# pulseHPT.net
KiCad netlist of a schematic drawn in EAGLE
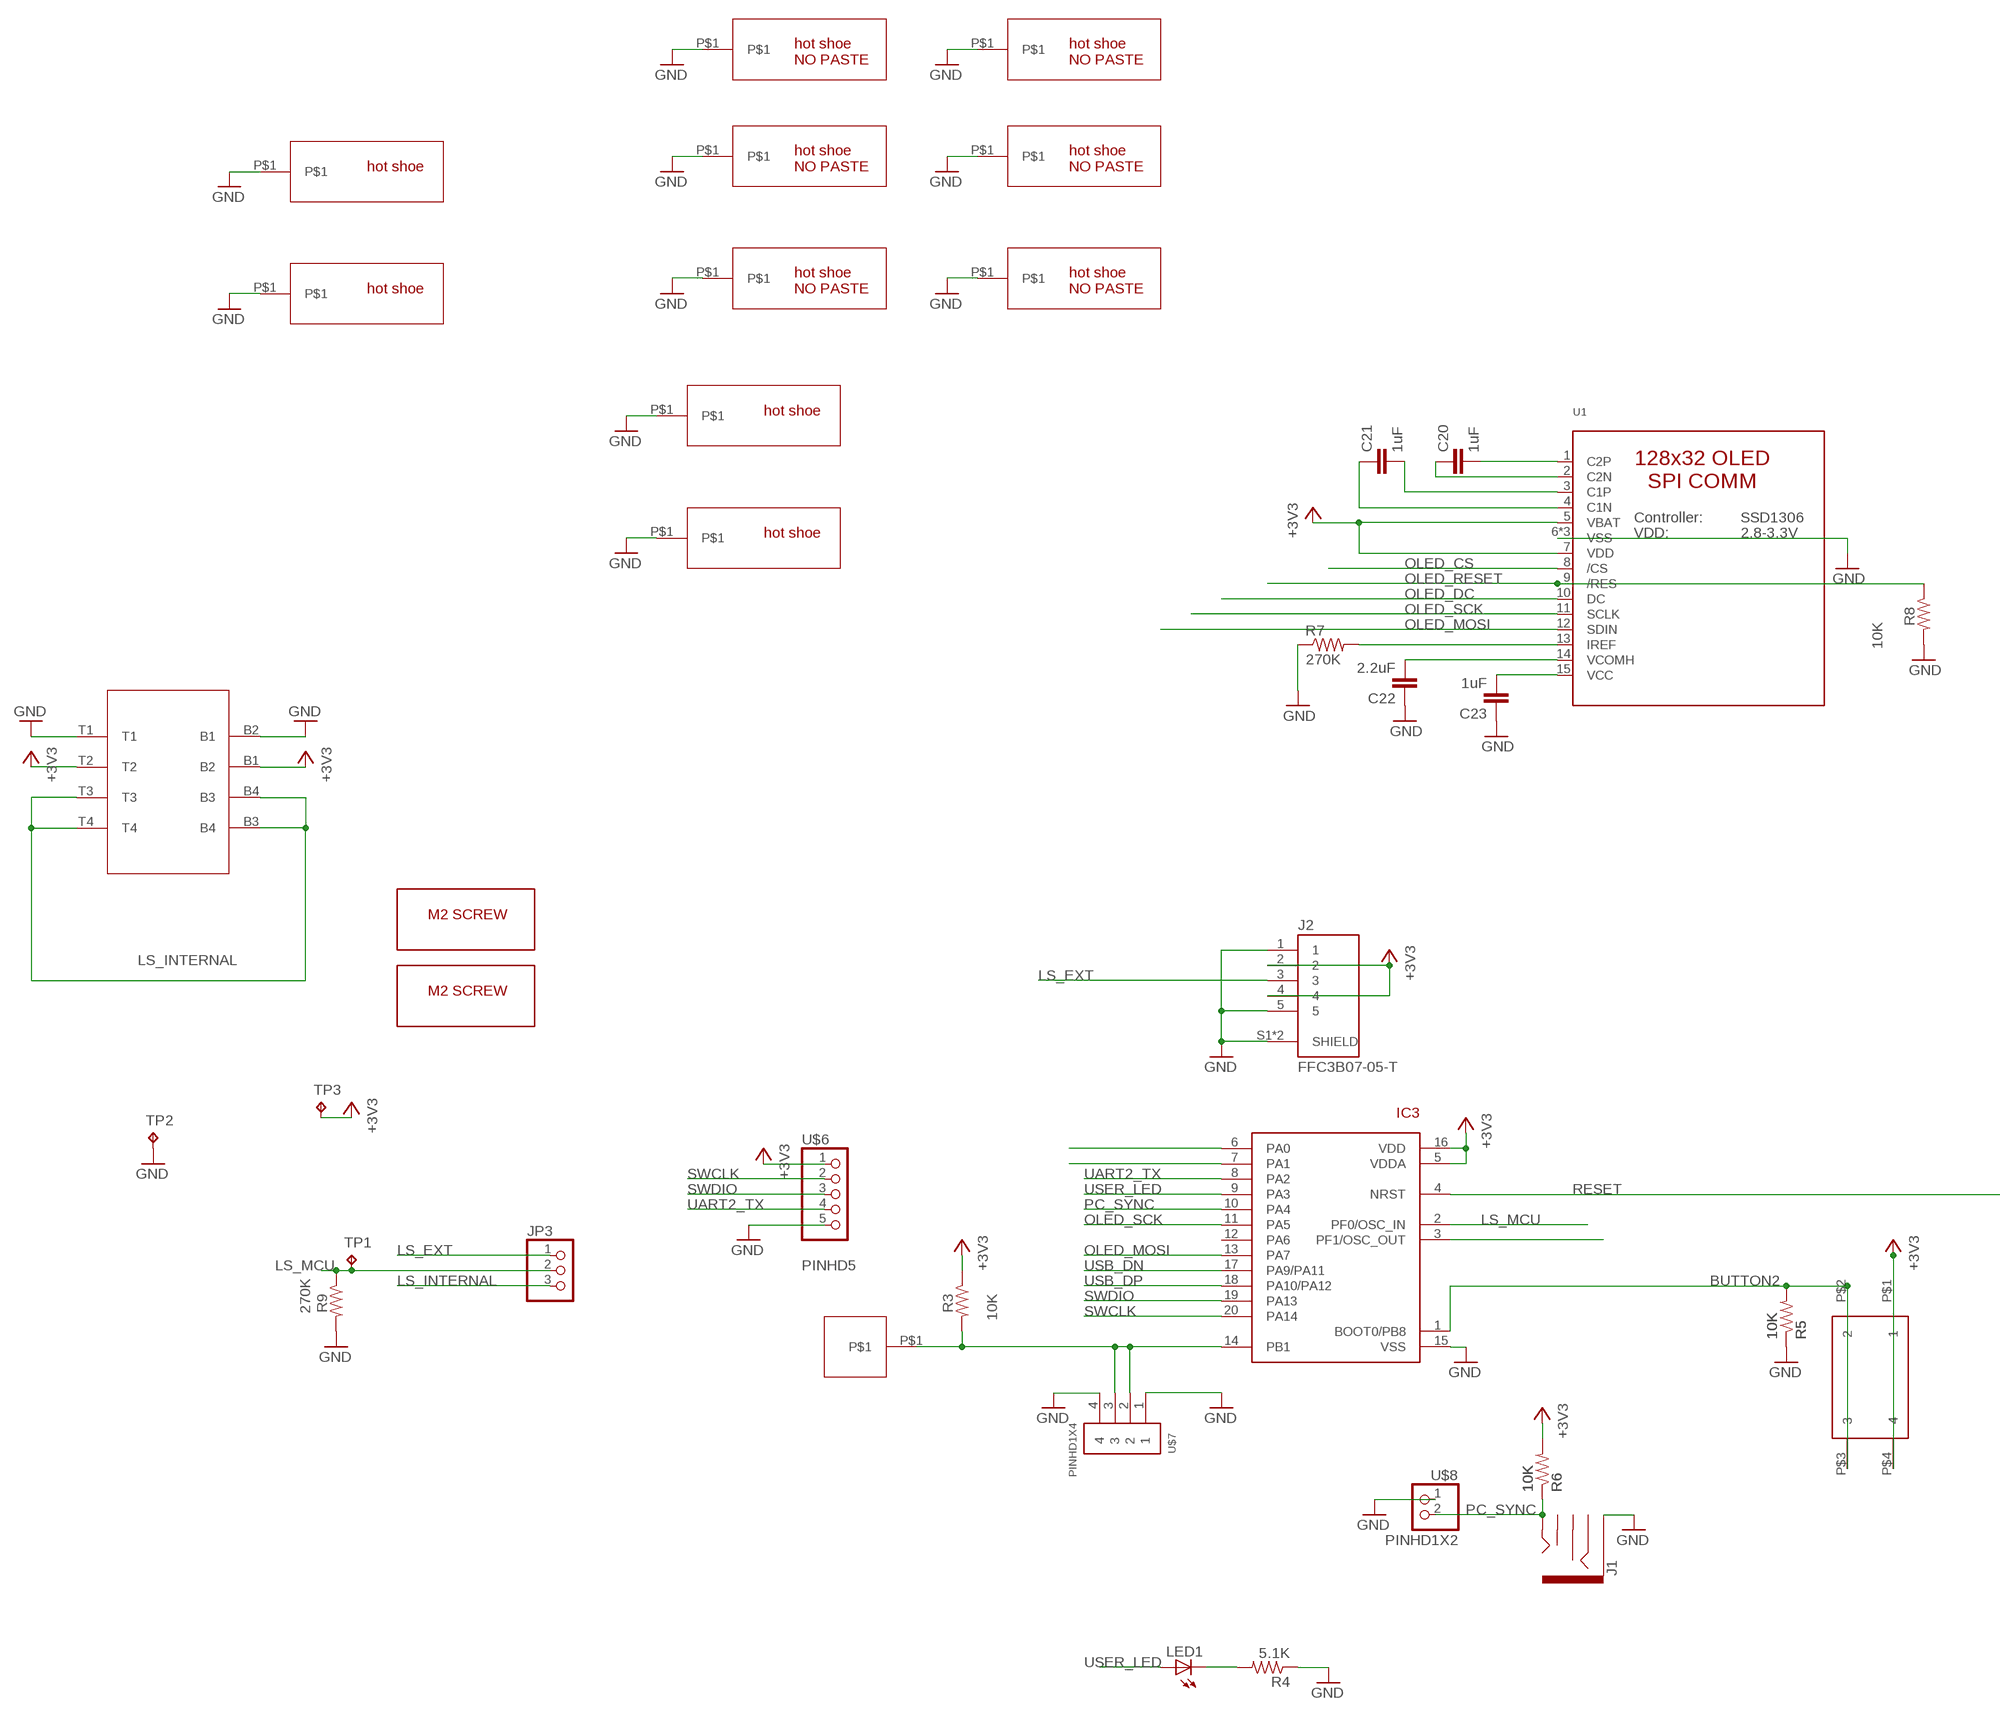
[diagram p0: schematic, sheet 1, part 1 of 2]
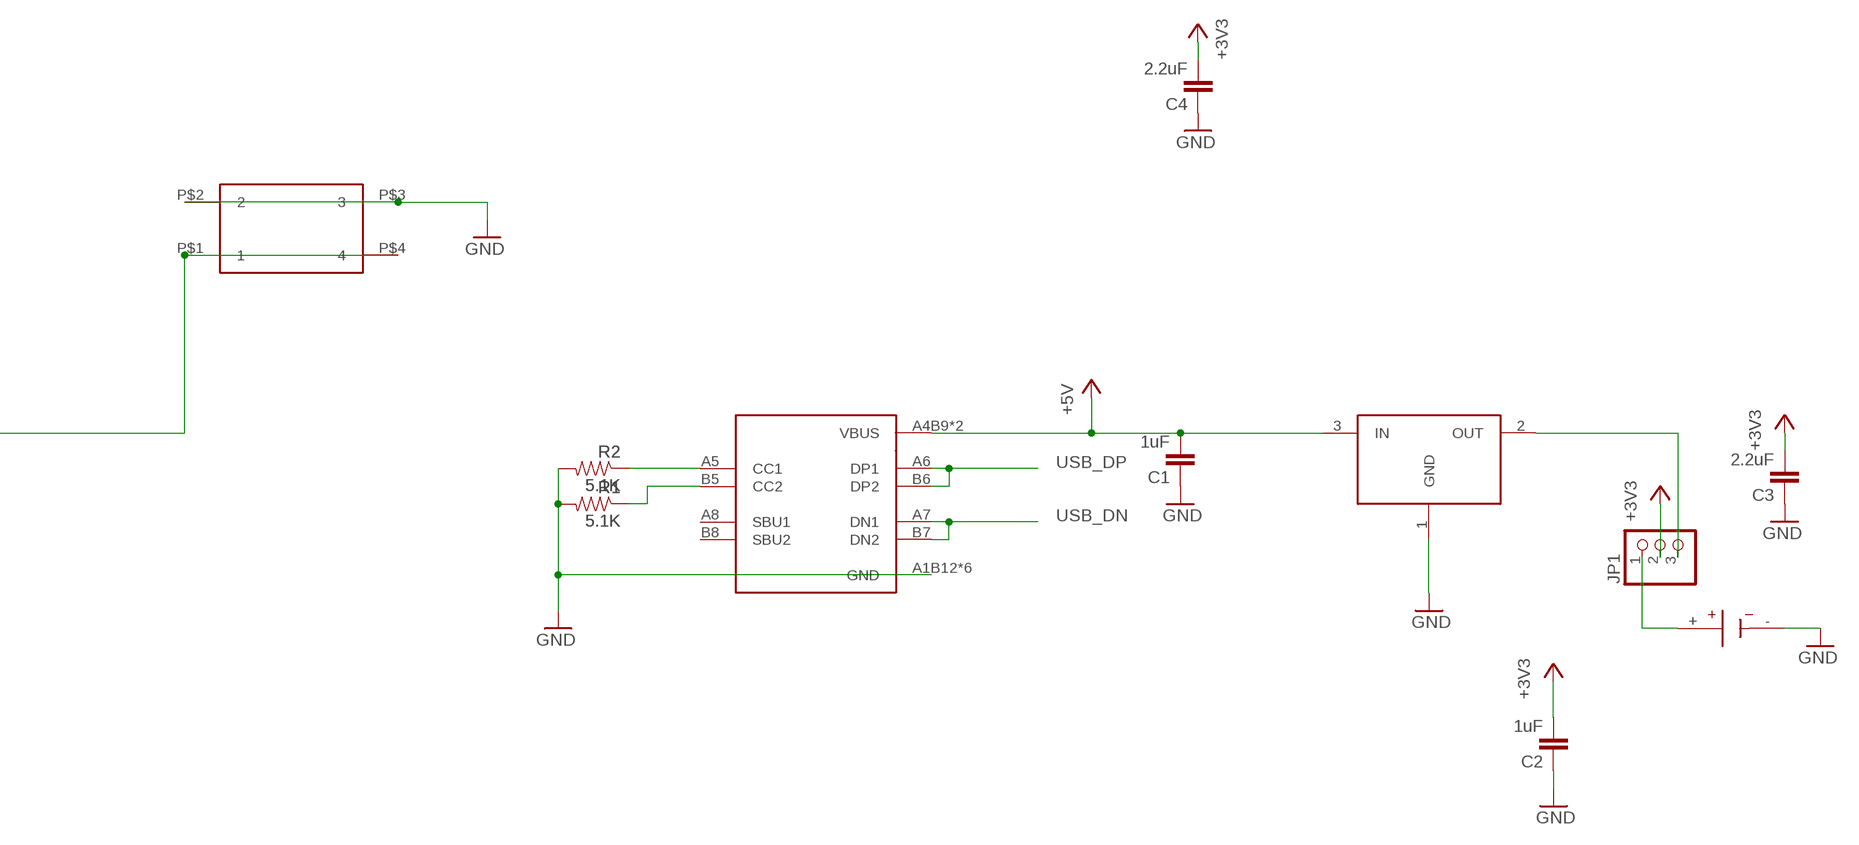
[diagram p1: schematic, sheet 1, part 2 of 2]

(export (version "E")
  (design (tool "Eeschema 10.0.6"))
  (components
    (comp (ref "BT1")
      (value "BU2032SM-G")
      (footprint "eagle-import:BAT_BU2032SM-G")
      (fields (field (name "MF") "MPD"))
      (libsource (lib "eagle-import") (part "BU2032SM-G"))
    )
    (comp (ref "C1")
      (value "1uF")
      (footprint "eagle-import:0805")
      (libsource (lib "eagle-import") (part "CAP0805"))
    )
    (comp (ref "C2")
      (value "1uF")
      (footprint "eagle-import:0805")
      (libsource (lib "eagle-import") (part "CAP0805"))
    )
    (comp (ref "C3")
      (value "2.2uF")
      (footprint "eagle-import:0805")
      (libsource (lib "eagle-import") (part "CAP0805"))
    )
    (comp (ref "C4")
      (value "2.2uF")
      (footprint "eagle-import:0805")
      (libsource (lib "eagle-import") (part "CAP0805"))
    )
    (comp (ref "C20")
      (value "1uF")
      (footprint "eagle-import:0805")
      (libsource (lib "eagle-import") (part "CAP0805"))
    )
    (comp (ref "C21")
      (value "1uF")
      (footprint "eagle-import:0805")
      (libsource (lib "eagle-import") (part "CAP0805"))
    )
    (comp (ref "C22")
      (value "2.2uF")
      (footprint "eagle-import:0805")
      (libsource (lib "eagle-import") (part "CAP0805"))
    )
    (comp (ref "C23")
      (value "1uF")
      (footprint "eagle-import:0805")
      (libsource (lib "eagle-import") (part "CAP0805"))
    )
    (comp (ref "IC3")
      (value "STM32F042F4")
      (footprint "eagle-import:TSSOP20")
      (libsource (lib "eagle-import") (part "STM32F042F4"))
    )
    (comp (ref "J1")
      (value "AUDIO_JACK_3.5MM_PTH")
      (footprint "eagle-import:AUDIO-JACK")
      (libsource (lib "eagle-import") (part "AUDIO_JACK_3.5MM_PTH"))
    )
    (comp (ref "J2")
      (value "FFC3B07-05-T")
      (footprint "eagle-import:GCT_FFC3B07-05-T")
      (fields (field (name "MF") "Global Connector Technology"))
      (libsource (lib "eagle-import") (part "FFC3B07-05-T"))
    )
    (comp (ref "JP1")
      (value "PINHD-1X3CB")
      (footprint "eagle-import:1X03-CLEANBIG")
      (libsource (lib "eagle-import") (part "PINHD-1X3CB"))
    )
    (comp (ref "JP3")
      (value "PINHD-1X3CB")
      (footprint "eagle-import:1X03-CLEANBIG")
      (libsource (lib "eagle-import") (part "PINHD-1X3CB"))
    )
    (comp (ref "LED1")
      (value "LEDCHIP-LED0805")
      (footprint "eagle-import:CHIP-LED0805")
      (libsource (lib "eagle-import") (part "LEDCHIP-LED0805"))
    )
    (comp (ref "R1")
      (value "5.1K")
      (footprint "eagle-import:0805")
      (libsource (lib "eagle-import") (part "joyAnalog_RESISTOR0805-RES"))
    )
    (comp (ref "R2")
      (value "5.1K")
      (footprint "eagle-import:0805")
      (libsource (lib "eagle-import") (part "joyAnalog_RESISTOR0805-RES"))
    )
    (comp (ref "R3")
      (value "10K")
      (footprint "eagle-import:0805")
      (libsource (lib "eagle-import") (part "joyAnalog_RESISTOR0805-RES"))
    )
    (comp (ref "R4")
      (value "5.1K")
      (footprint "eagle-import:0805")
      (libsource (lib "eagle-import") (part "RESISTOR0805-RES"))
    )
    (comp (ref "R5")
      (value "10K")
      (footprint "eagle-import:0805")
      (libsource (lib "eagle-import") (part "joyAnalog_RESISTOR0805-RES"))
    )
    (comp (ref "R6")
      (value "10K")
      (footprint "eagle-import:0805")
      (libsource (lib "eagle-import") (part "joyAnalog_RESISTOR0805-RES"))
    )
    (comp (ref "R7")
      (value "270K")
      (footprint "eagle-import:0805")
      (libsource (lib "eagle-import") (part "RESISTOR0805-RES"))
    )
    (comp (ref "R8")
      (value "10K")
      (footprint "eagle-import:0805")
      (libsource (lib "eagle-import") (part "joyAnalog_RESISTOR0805-RES"))
    )
    (comp (ref "R9")
      (value "270K")
      (footprint "eagle-import:0805")
      (libsource (lib "eagle-import") (part "joyAnalog_RESISTOR0805-RES"))
    )
    (comp (ref "SW3")
      (value "324_SW324_SWITCH_FOOT_HOLE")
      (footprint "eagle-import:342_SWICH_FOOT_HOLE")
      (libsource (lib "eagle-import") (part "324_SW324_SWITCH_FOOT_HOLE"))
    )
    (comp (ref "SW4")
      (value "324_SW")
      (footprint "eagle-import:342_SWICH_FOOT")
      (libsource (lib "eagle-import") (part "3pos_slide_switch_centered_324_SW"))
    )
    (comp (ref "TP1")
      (value "TPTP18R")
      (footprint "eagle-import:TP18R")
      (libsource (lib "eagle-import") (part "TPTP18R"))
    )
    (comp (ref "TP2")
      (value "TPTP18R")
      (footprint "eagle-import:TP18R")
      (libsource (lib "eagle-import") (part "TPTP18R"))
    )
    (comp (ref "TP3")
      (value "TPTP18R")
      (footprint "eagle-import:TP18R")
      (libsource (lib "eagle-import") (part "TPTP18R"))
    )
    (comp (ref "U$1")
      (value "M2_SCREW_DEV")
      (footprint "eagle-import:M2_SCREW_FOOT")
      (libsource (lib "eagle-import") (part "M2_SCREW_DEV"))
    )
    (comp (ref "U$2")
      (value "SPRING_CONTACT")
      (footprint "eagle-import:SPRING_CONTACT")
      (libsource (lib "eagle-import") (part "SPRING_CONTACT"))
    )
    (comp (ref "U$3")
      (value "HOTSHOE")
      (footprint "eagle-import:HOTSHOE_RAIL")
      (libsource (lib "eagle-import") (part "HOTSHOE"))
    )
    (comp (ref "U$4")
      (value "HOTSHOE")
      (footprint "eagle-import:HOTSHOE_RAIL")
      (libsource (lib "eagle-import") (part "HOTSHOE"))
    )
    (comp (ref "U$5")
      (value "HOTSHOE_NOPASTE")
      (footprint "eagle-import:HOTSHOE_RAIL_NOPASTE")
      (libsource (lib "eagle-import") (part "HOTSHOE_NOPASTE"))
    )
    (comp (ref "U$6")
      (value "PINHD5")
      (footprint "eagle-import:1X05")
      (libsource (lib "eagle-import") (part "PINHD5"))
    )
    (comp (ref "U$7")
      (value "PINHD1X4")
      (footprint "eagle-import:1X04-CLEANBIG")
      (libsource (lib "eagle-import") (part "PINHD1X4"))
    )
    (comp (ref "U$8")
      (value "PINHD1X2")
      (footprint "eagle-import:1X02")
      (libsource (lib "eagle-import") (part "PINHD1X2"))
    )
    (comp (ref "U$9")
      (value "HOTSHOE_NOPASTE")
      (footprint "eagle-import:HOTSHOE_RAIL_NOPASTE")
      (libsource (lib "eagle-import") (part "HOTSHOE_NOPASTE"))
    )
    (comp (ref "U$10")
      (value "HOTSHOE_NOPASTE")
      (footprint "eagle-import:HOTSHOE_RAIL_NOPASTE")
      (libsource (lib "eagle-import") (part "HOTSHOE_NOPASTE"))
    )
    (comp (ref "U$11")
      (value "HOTSHOE_NOPASTE")
      (footprint "eagle-import:HOTSHOE_RAIL_NOPASTE")
      (libsource (lib "eagle-import") (part "HOTSHOE_NOPASTE"))
    )
    (comp (ref "U$12")
      (value "M2_SCREW_DEV")
      (footprint "eagle-import:M2_SCREW_FOOT")
      (libsource (lib "eagle-import") (part "M2_SCREW_DEV"))
    )
    (comp (ref "U$13")
      (value "HOTSHOE_NOPASTE")
      (footprint "eagle-import:HOTSHOE_RAIL_NOPASTE")
      (libsource (lib "eagle-import") (part "HOTSHOE_NOPASTE"))
    )
    (comp (ref "U$14")
      (value "HOTSHOE")
      (footprint "eagle-import:HOTSHOE_RAIL")
      (libsource (lib "eagle-import") (part "HOTSHOE"))
    )
    (comp (ref "U$15")
      (value "HOTSHOE_NOPASTE")
      (footprint "eagle-import:HOTSHOE_RAIL_NOPASTE")
      (libsource (lib "eagle-import") (part "HOTSHOE_NOPASTE"))
    )
    (comp (ref "U$16")
      (value "HOTSHOE")
      (footprint "eagle-import:HOTSHOE_RAIL")
      (libsource (lib "eagle-import") (part "HOTSHOE"))
    )
    (comp (ref "U$17")
      (value "LS_HOLE")
      (footprint "eagle-import:LS")
      (libsource (lib "eagle-import") (part "LS_HOLE"))
    )
    (comp (ref "U1")
      (value "LUL_DISP_OLED_UG-2864HSWEG01")
      (footprint "eagle-import:LUL_UG-2864HSWEG01_1.3_WRAPAROUND")
      (libsource (lib "eagle-import") (part "LUL_DISP_OLED_UG-2864HSWEG01"))
    )
    (comp (ref "U2")
      (value "USBC_16P")
      (footprint "eagle-import:USBC_16P_FOOT")
      (libsource (lib "eagle-import") (part "USBC_16P"))
    )
    (comp (ref "U4")
      (value "XC6206_DEV")
      (footprint "eagle-import:SOT23R_INFINEON")
      (libsource (lib "eagle-import") (part "XC6206_DEV"))
    )
  )
  (nets
    (net (code "1") (name "+3V3") (class "Default")
      (node (ref "C2") (pin "2") (pinfunction "2_2") (pintype "passive"))
      (node (ref "C3") (pin "2") (pinfunction "2_2") (pintype "passive"))
      (node (ref "C4") (pin "2") (pinfunction "2_2") (pintype "passive"))
      (node (ref "IC3") (pin "16") (pinfunction "VDD_16") (pintype "bidirectional"))
      (node (ref "IC3") (pin "5") (pinfunction "VDDA_5") (pintype "bidirectional"))
      (node (ref "J2") (pin "2") (pinfunction "2_2") (pintype "passive"))
      (node (ref "J2") (pin "4") (pinfunction "4_4") (pintype "passive"))
      (node (ref "JP1") (pin "2") (pinfunction "2_2") (pintype "passive"))
      (node (ref "R3") (pin "1") (pinfunction "1_1") (pintype "passive"))
      (node (ref "R6") (pin "2") (pinfunction "2_2") (pintype "passive"))
      (node (ref "SW4") (pin "P$1") (pinfunction "1_P$1") (pintype "bidirectional"))
      (node (ref "SW4") (pin "P$4") (pinfunction "4_P$4") (pintype "bidirectional"))
      (node (ref "TP3") (pin "TP") (pinfunction "TP_TP") (pintype "input"))
      (node (ref "U$17") (pin "B1") (pinfunction "B2_B1") (pintype "bidirectional"))
      (node (ref "U$17") (pin "T2") (pinfunction "T2_T2") (pintype "bidirectional"))
      (node (ref "U$6") (pin "1") (pinfunction "1_1") (pintype "passive"))
      (node (ref "U1") (pin "5") (pinfunction "VBAT_5") (pintype "input"))
      (node (ref "U1") (pin "7") (pinfunction "VDD_7") (pintype "power_in"))
    )
    (net (code "2") (name "+5V") (class "Default")
      (node (ref "C1") (pin "2") (pinfunction "2_2") (pintype "passive"))
      (node (ref "U2") (pin "A4B9") (pinfunction "VBUS_A4B9") (pintype "bidirectional"))
      (node (ref "U2") (pin "B4A9") (pinfunction "VBUS_B4A9") (pintype "bidirectional"))
      (node (ref "U4") (pin "3") (pinfunction "IN_3") (pintype "bidirectional"))
    )
    (net (code "3") (name "/BUTTON2") (class "Default")
      (node (ref "IC3") (pin "1") (pinfunction "BOOT0/PB8_1") (pintype "bidirectional"))
      (node (ref "R5") (pin "2") (pinfunction "2_2") (pintype "passive"))
      (node (ref "SW4") (pin "P$2") (pinfunction "2_P$2") (pintype "bidirectional"))
      (node (ref "SW4") (pin "P$3") (pinfunction "3_P$3") (pintype "bidirectional"))
    )
    (net (code "4") (name "/LS_EXT") (class "Default")
      (node (ref "J2") (pin "3") (pinfunction "3_3") (pintype "passive"))
      (node (ref "JP3") (pin "1") (pinfunction "1_1") (pintype "passive"))
    )
    (net (code "5") (name "/LS_INTERNAL") (class "Default")
      (node (ref "JP3") (pin "3") (pinfunction "3_3") (pintype "passive"))
      (node (ref "U$17") (pin "B3") (pinfunction "B4_B3") (pintype "bidirectional"))
      (node (ref "U$17") (pin "B4") (pinfunction "B3_B4") (pintype "bidirectional"))
      (node (ref "U$17") (pin "T3") (pinfunction "T3_T3") (pintype "bidirectional"))
      (node (ref "U$17") (pin "T4") (pinfunction "T4_T4") (pintype "bidirectional"))
    )
    (net (code "6") (name "/LS_MCU") (class "Default")
      (node (ref "IC3") (pin "2") (pinfunction "PF0/OSC_IN_2") (pintype "bidirectional"))
      (node (ref "JP3") (pin "2") (pinfunction "2_2") (pintype "passive"))
      (node (ref "R9") (pin "1") (pinfunction "1_1") (pintype "passive"))
      (node (ref "TP1") (pin "TP") (pinfunction "TP_TP") (pintype "input"))
    )
    (net (code "7") (name "/OLED_CS") (class "Default")
      (node (ref "IC3") (pin "3") (pinfunction "PF1/OSC_OUT_3") (pintype "bidirectional"))
      (node (ref "U1") (pin "8") (pinfunction "/CS_8") (pintype "input"))
    )
    (net (code "8") (name "/OLED_DC") (class "Default")
      (node (ref "IC3") (pin "7") (pinfunction "PA1_7") (pintype "bidirectional"))
      (node (ref "U1") (pin "10") (pinfunction "DC_10") (pintype "input"))
    )
    (net (code "9") (name "/OLED_MOSI") (class "Default")
      (node (ref "IC3") (pin "13") (pinfunction "PA7_13") (pintype "bidirectional"))
      (node (ref "U1") (pin "12") (pinfunction "SDIN_12") (pintype "bidirectional"))
    )
    (net (code "10") (name "/OLED_RESET") (class "Default")
      (node (ref "IC3") (pin "6") (pinfunction "PA0_6") (pintype "bidirectional"))
      (node (ref "R8") (pin "1") (pinfunction "1_1") (pintype "passive"))
      (node (ref "U1") (pin "9") (pinfunction "/RES_9") (pintype "input"))
    )
    (net (code "11") (name "/OLED_SCK") (class "Default")
      (node (ref "IC3") (pin "11") (pinfunction "PA5_11") (pintype "bidirectional"))
      (node (ref "U1") (pin "11") (pinfunction "SCLK_11") (pintype "bidirectional"))
    )
    (net (code "12") (name "/PC_SYNC") (class "Default")
      (node (ref "IC3") (pin "10") (pinfunction "PA4_10") (pintype "bidirectional"))
      (node (ref "J1") (pin "TIP") (pinfunction "TIP_TIP") (pintype "bidirectional"))
      (node (ref "R6") (pin "1") (pinfunction "1_1") (pintype "passive"))
      (node (ref "U$8") (pin "2") (pinfunction "2_2") (pintype "passive"))
    )
    (net (code "13") (name "/RESET") (class "Default")
      (node (ref "IC3") (pin "4") (pinfunction "NRST_4") (pintype "bidirectional"))
      (node (ref "SW3") (pin "P$1") (pinfunction "1_P$1") (pintype "bidirectional"))
      (node (ref "SW3") (pin "P$4") (pinfunction "4_P$4") (pintype "bidirectional"))
    )
    (net (code "14") (name "/SWCLK") (class "Default")
      (node (ref "IC3") (pin "20") (pinfunction "PA14_20") (pintype "bidirectional"))
      (node (ref "U$6") (pin "2") (pinfunction "2_2") (pintype "passive"))
    )
    (net (code "15") (name "/SWDIO") (class "Default")
      (node (ref "IC3") (pin "19") (pinfunction "PA13_19") (pintype "bidirectional"))
      (node (ref "U$6") (pin "3") (pinfunction "3_3") (pintype "passive"))
    )
    (net (code "16") (name "/UART2_TX") (class "Default")
      (node (ref "IC3") (pin "8") (pinfunction "PA2_8") (pintype "bidirectional"))
      (node (ref "U$6") (pin "4") (pinfunction "4_4") (pintype "passive"))
    )
    (net (code "17") (name "/USB_DN") (class "Default")
      (node (ref "IC3") (pin "17") (pinfunction "PA9/PA11_17") (pintype "bidirectional"))
      (node (ref "U2") (pin "A7") (pinfunction "DN1_A7") (pintype "bidirectional"))
      (node (ref "U2") (pin "B7") (pinfunction "DN2_B7") (pintype "bidirectional"))
    )
    (net (code "18") (name "/USB_DP") (class "Default")
      (node (ref "IC3") (pin "18") (pinfunction "PA10/PA12_18") (pintype "bidirectional"))
      (node (ref "U2") (pin "A6") (pinfunction "DP1_A6") (pintype "bidirectional"))
      (node (ref "U2") (pin "B6") (pinfunction "DP2_B6") (pintype "bidirectional"))
    )
    (net (code "19") (name "/USER_LED") (class "Default")
      (node (ref "IC3") (pin "9") (pinfunction "PA3_9") (pintype "bidirectional"))
      (node (ref "LED1") (pin "A") (pinfunction "A_A") (pintype "passive"))
    )
    (net (code "20") (name "GND") (class "Default")
      (node (ref "BT1") (pin "-") (pinfunction "-_-") (pintype "passive"))
      (node (ref "C1") (pin "1") (pinfunction "1_1") (pintype "passive"))
      (node (ref "C2") (pin "1") (pinfunction "1_1") (pintype "passive"))
      (node (ref "C22") (pin "1") (pinfunction "1_1") (pintype "passive"))
      (node (ref "C23") (pin "1") (pinfunction "1_1") (pintype "passive"))
      (node (ref "C3") (pin "1") (pinfunction "1_1") (pintype "passive"))
      (node (ref "C4") (pin "1") (pinfunction "1_1") (pintype "passive"))
      (node (ref "IC3") (pin "15") (pinfunction "VSS_15") (pintype "bidirectional"))
      (node (ref "J1") (pin "SLEEVE") (pinfunction "SLEEVE_SLEEVE") (pintype "bidirectional"))
      (node (ref "J2") (pin "1") (pinfunction "1_1") (pintype "passive"))
      (node (ref "J2") (pin "5") (pinfunction "5_5") (pintype "passive"))
      (node (ref "J2") (pin "S1") (pinfunction "SHIELD_S1") (pintype "passive"))
      (node (ref "J2") (pin "S2") (pinfunction "SHIELD_S2") (pintype "passive"))
      (node (ref "R1") (pin "2") (pinfunction "2_2") (pintype "passive"))
      (node (ref "R2") (pin "2") (pinfunction "2_2") (pintype "passive"))
      (node (ref "R4") (pin "1") (pinfunction "1_1") (pintype "passive"))
      (node (ref "R5") (pin "1") (pinfunction "1_1") (pintype "passive"))
      (node (ref "R7") (pin "1") (pinfunction "1_1") (pintype "passive"))
      (node (ref "R8") (pin "2") (pinfunction "2_2") (pintype "passive"))
      (node (ref "R9") (pin "2") (pinfunction "2_2") (pintype "passive"))
      (node (ref "SW3") (pin "P$2") (pinfunction "2_P$2") (pintype "bidirectional"))
      (node (ref "SW3") (pin "P$3") (pinfunction "3_P$3") (pintype "bidirectional"))
      (node (ref "TP2") (pin "TP") (pinfunction "TP_TP") (pintype "input"))
      (node (ref "U$10") (pin "P$1") (pinfunction "P$1_P$1") (pintype "bidirectional"))
      (node (ref "U$11") (pin "P$1") (pinfunction "P$1_P$1") (pintype "bidirectional"))
      (node (ref "U$13") (pin "P$1") (pinfunction "P$1_P$1") (pintype "bidirectional"))
      (node (ref "U$14") (pin "P$1") (pinfunction "P$1_P$1") (pintype "bidirectional"))
      (node (ref "U$15") (pin "P$1") (pinfunction "P$1_P$1") (pintype "bidirectional"))
      (node (ref "U$16") (pin "P$1") (pinfunction "P$1_P$1") (pintype "bidirectional"))
      (node (ref "U$17") (pin "B2") (pinfunction "B1_B2") (pintype "bidirectional"))
      (node (ref "U$17") (pin "T1") (pinfunction "T1_T1") (pintype "bidirectional"))
      (node (ref "U$3") (pin "P$1") (pinfunction "P$1_P$1") (pintype "bidirectional"))
      (node (ref "U$4") (pin "P$1") (pinfunction "P$1_P$1") (pintype "bidirectional"))
      (node (ref "U$5") (pin "P$1") (pinfunction "P$1_P$1") (pintype "bidirectional"))
      (node (ref "U$6") (pin "5") (pinfunction "5_5") (pintype "passive"))
      (node (ref "U$7") (pin "1") (pinfunction "1_1") (pintype "bidirectional"))
      (node (ref "U$7") (pin "4") (pinfunction "4_4") (pintype "bidirectional"))
      (node (ref "U$8") (pin "1") (pinfunction "1_1") (pintype "passive"))
      (node (ref "U$9") (pin "P$1") (pinfunction "P$1_P$1") (pintype "bidirectional"))
      (node (ref "U1") (pin "16") (pinfunction "VSS_16") (pintype "power_in"))
      (node (ref "U1") (pin "17") (pinfunction "VSS_17") (pintype "power_in"))
      (node (ref "U1") (pin "6") (pinfunction "VSS_6") (pintype "power_in"))
      (node (ref "U2") (pin "A1B12") (pinfunction "GND_A1B12") (pintype "bidirectional"))
      (node (ref "U2") (pin "B11A12") (pinfunction "GND_B11A12") (pintype "bidirectional"))
      (node (ref "U2") (pin "P$13") (pinfunction "GND_P$13") (pintype "bidirectional"))
      (node (ref "U2") (pin "P$14") (pinfunction "GND_P$14") (pintype "bidirectional"))
      (node (ref "U2") (pin "P$15") (pinfunction "GND_P$15") (pintype "bidirectional"))
      (node (ref "U2") (pin "P$16") (pinfunction "GND_P$16") (pintype "bidirectional"))
      (node (ref "U4") (pin "1") (pinfunction "GND_1") (pintype "bidirectional"))
    )
    (net (code "21") (name "Net-(BT1-Pad+)") (class "Default")
      (node (ref "BT1") (pin "+") (pinfunction "+_+") (pintype "passive"))
      (node (ref "JP1") (pin "1") (pinfunction "1_1") (pintype "passive"))
    )
    (net (code "22") (name "Net-(IC3-PB1)") (class "Default")
      (node (ref "IC3") (pin "14") (pinfunction "PB1_14") (pintype "bidirectional"))
      (node (ref "R3") (pin "2") (pinfunction "2_2") (pintype "passive"))
      (node (ref "U$2") (pin "P$1") (pinfunction "P$1_P$1") (pintype "bidirectional"))
      (node (ref "U$7") (pin "2") (pinfunction "2_2") (pintype "bidirectional"))
      (node (ref "U$7") (pin "3") (pinfunction "3_3") (pintype "bidirectional"))
    )
    (net (code "23") (name "Net-(LED1-PadC)") (class "Default")
      (node (ref "LED1") (pin "C") (pinfunction "C_C") (pintype "passive"))
      (node (ref "R4") (pin "2") (pinfunction "2_2") (pintype "passive"))
    )
    (net (code "24") (name "Net-(U1-C1N)") (class "Default")
      (node (ref "C21") (pin "1") (pinfunction "1_1") (pintype "passive"))
      (node (ref "U1") (pin "4") (pinfunction "C1N_4") (pintype "input"))
    )
    (net (code "25") (name "Net-(U1-C1P)") (class "Default")
      (node (ref "C21") (pin "2") (pinfunction "2_2") (pintype "passive"))
      (node (ref "U1") (pin "3") (pinfunction "C1P_3") (pintype "input"))
    )
    (net (code "26") (name "Net-(U1-C2N)") (class "Default")
      (node (ref "C20") (pin "1") (pinfunction "1_1") (pintype "passive"))
      (node (ref "U1") (pin "2") (pinfunction "C2N_2") (pintype "input"))
    )
    (net (code "27") (name "Net-(U1-C2P)") (class "Default")
      (node (ref "C20") (pin "2") (pinfunction "2_2") (pintype "passive"))
      (node (ref "U1") (pin "1") (pinfunction "C2P_1") (pintype "input"))
    )
    (net (code "28") (name "Net-(U1-IREF)") (class "Default")
      (node (ref "R7") (pin "2") (pinfunction "2_2") (pintype "passive"))
      (node (ref "U1") (pin "13") (pinfunction "IREF_13") (pintype "input"))
    )
    (net (code "29") (name "Net-(U1-VCC)") (class "Default")
      (node (ref "C23") (pin "2") (pinfunction "2_2") (pintype "passive"))
      (node (ref "U1") (pin "15") (pinfunction "VCC_15") (pintype "power_in"))
    )
    (net (code "30") (name "Net-(U1-VCOMH)") (class "Default")
      (node (ref "C22") (pin "2") (pinfunction "2_2") (pintype "passive"))
      (node (ref "U1") (pin "14") (pinfunction "VCOMH_14") (pintype "output"))
    )
    (net (code "31") (name "Net-(U2-CC1)") (class "Default")
      (node (ref "R2") (pin "1") (pinfunction "1_1") (pintype "passive"))
      (node (ref "U2") (pin "A5") (pinfunction "CC1_A5") (pintype "bidirectional"))
    )
    (net (code "32") (name "Net-(U2-CC2)") (class "Default")
      (node (ref "R1") (pin "1") (pinfunction "1_1") (pintype "passive"))
      (node (ref "U2") (pin "B5") (pinfunction "CC2_B5") (pintype "bidirectional"))
    )
    (net (code "33") (name "Net-(U4-OUT)") (class "Default")
      (node (ref "JP1") (pin "3") (pinfunction "3_3") (pintype "passive"))
      (node (ref "U4") (pin "2") (pinfunction "OUT_2") (pintype "bidirectional"))
    )
    (net (code "34") (name "unconnected-(IC3-PA6-Pad12)") (class "Default")
      (node (ref "IC3") (pin "12") (pinfunction "PA6_12") (pintype "bidirectional"))
    )
    (net (code "35") (name "unconnected-(J1-PadRING)") (class "Default")
      (node (ref "J1") (pin "RING") (pinfunction "RING_RING") (pintype "bidirectional"))
    )
    (net (code "36") (name "unconnected-(J1-PadRSH)") (class "Default")
      (node (ref "J1") (pin "RSH") (pinfunction "RSH_RSH") (pintype "bidirectional"))
    )
    (net (code "37") (name "unconnected-(J1-PadTSH)") (class "Default")
      (node (ref "J1") (pin "TSH") (pinfunction "TSH_TSH") (pintype "bidirectional"))
    )
    (net (code "38") (name "unconnected-(U2-SBU1-PadA8)") (class "Default")
      (node (ref "U2") (pin "A8") (pinfunction "SBU1_A8") (pintype "bidirectional"))
    )
    (net (code "39") (name "unconnected-(U2-SBU2-PadB8)") (class "Default")
      (node (ref "U2") (pin "B8") (pinfunction "SBU2_B8") (pintype "bidirectional"))
    )
  )
)
